# CSR8635-V1_4.net
KiCad netlist of a schematic drawn in EAGLE
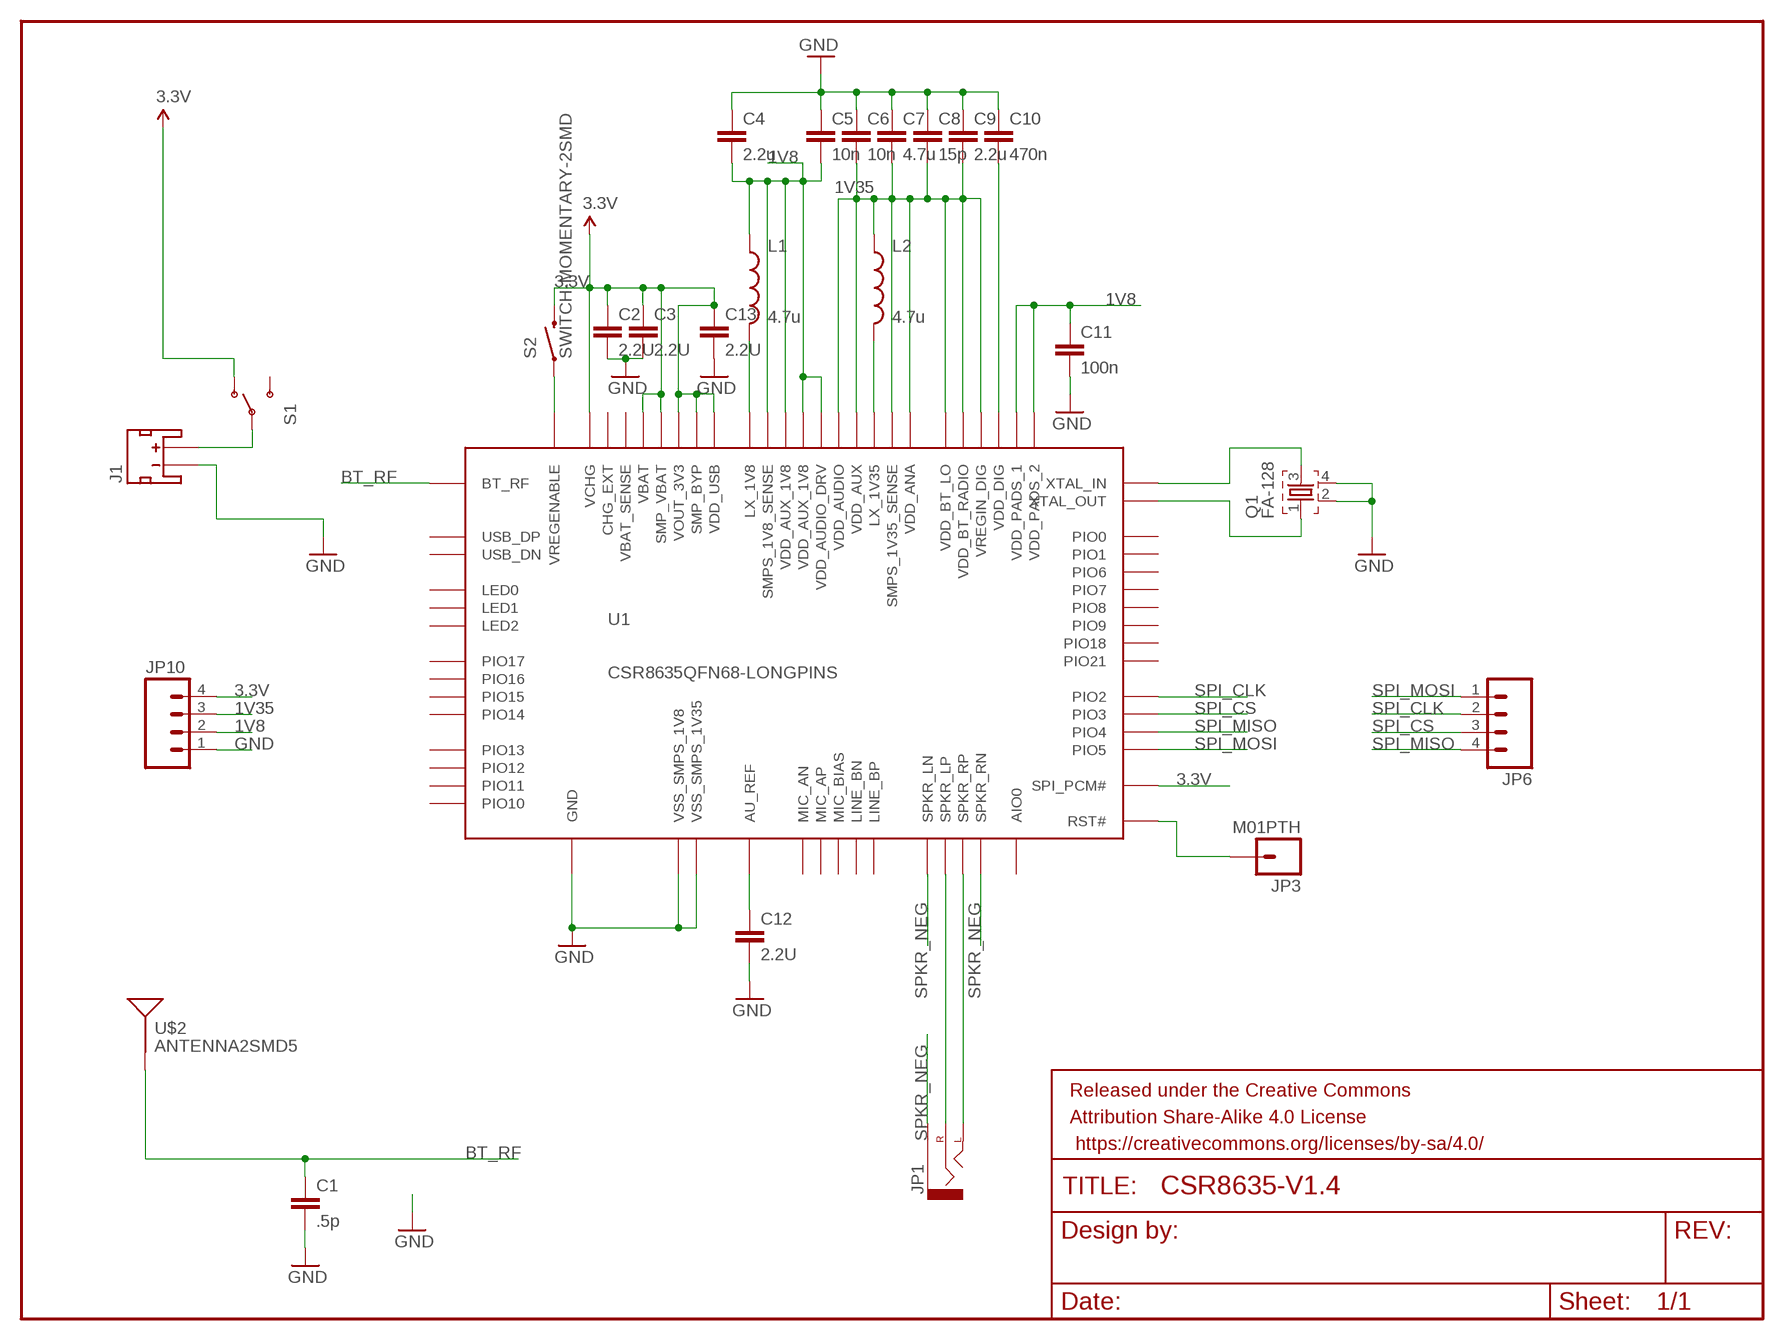
[diagram p0: schematic, sheet 1]

(export (version "E")
  (design (tool "Eeschema 10.0.6"))
  (components
    (comp (ref "C1")
      (value ".5p")
      (footprint "eagle-import:0603-CAP")
      (libsource (lib "eagle-import") (part "CAP0603-CAP"))
    )
    (comp (ref "C2")
      (value "2.2U")
      (footprint "eagle-import:0603-CAP")
      (libsource (lib "eagle-import") (part "CAP0603-CAP"))
    )
    (comp (ref "C3")
      (value "2.2U")
      (footprint "eagle-import:0603-CAP")
      (libsource (lib "eagle-import") (part "CAP0603-CAP"))
    )
    (comp (ref "C4")
      (value "2.2u")
      (footprint "eagle-import:0603-CAP")
      (libsource (lib "eagle-import") (part "CAP0603-CAP"))
    )
    (comp (ref "C5")
      (value "10n")
      (footprint "eagle-import:0603-CAP")
      (libsource (lib "eagle-import") (part "CAP0603-CAP"))
    )
    (comp (ref "C6")
      (value "10n")
      (footprint "eagle-import:0603-CAP")
      (libsource (lib "eagle-import") (part "CAP0603-CAP"))
    )
    (comp (ref "C7")
      (value "4.7u")
      (footprint "eagle-import:0603-CAP")
      (libsource (lib "eagle-import") (part "CAP0603-CAP"))
    )
    (comp (ref "C8")
      (value "15p")
      (footprint "eagle-import:0603-CAP")
      (libsource (lib "eagle-import") (part "CAP0603-CAP"))
    )
    (comp (ref "C9")
      (value "2.2u")
      (footprint "eagle-import:0603-CAP")
      (libsource (lib "eagle-import") (part "CAP0603-CAP"))
    )
    (comp (ref "C10")
      (value "470n")
      (footprint "eagle-import:0603-CAP")
      (libsource (lib "eagle-import") (part "CAP0603-CAP"))
    )
    (comp (ref "C11")
      (value "100n")
      (footprint "eagle-import:0603-CAP")
      (libsource (lib "eagle-import") (part "CAP0603-CAP"))
    )
    (comp (ref "C12")
      (value "2.2U")
      (footprint "eagle-import:0603-CAP")
      (libsource (lib "eagle-import") (part "CAP0603-CAP"))
    )
    (comp (ref "C13")
      (value "2.2U")
      (footprint "eagle-import:0603-CAP")
      (libsource (lib "eagle-import") (part "CAP0603-CAP"))
    )
    (comp (ref "FRAME1")
      (value "FRAME-LETTER")
      (footprint "eagle-import:CREATIVE_COMMONS")
      (libsource (lib "eagle-import") (part "FRAME-LETTER"))
    )
    (comp (ref "J1")
      (value "JST_2MM_MALE")
      (footprint "eagle-import:JST-2-SMD")
      (libsource (lib "eagle-import") (part "JST_2MM_MALE"))
    )
    (comp (ref "JP1")
      (value "AUDIO-JACKSMD2")
      (footprint "eagle-import:AUDIO-JACK-3.5MM-SMD")
      (libsource (lib "eagle-import") (part "AUDIO-JACKSMD2"))
    )
    (comp (ref "JP3")
      (value "M01PTH")
      (footprint "eagle-import:1X01")
      (libsource (lib "eagle-import") (part "M01PTH"))
    )
    (comp (ref "JP6")
      (value "M04PTH")
      (footprint "eagle-import:1X04")
      (libsource (lib "eagle-import") (part "M04PTH"))
    )
    (comp (ref "JP10")
      (value "M04PTH")
      (footprint "eagle-import:1X04")
      (libsource (lib "eagle-import") (part "M04PTH"))
    )
    (comp (ref "L1")
      (value "4.7u")
      (footprint "eagle-import:0805")
      (libsource (lib "eagle-import") (part "INDUCTOR0805"))
    )
    (comp (ref "L2")
      (value "4.7u")
      (footprint "eagle-import:0805")
      (libsource (lib "eagle-import") (part "INDUCTOR0805"))
    )
    (comp (ref "Q1")
      (value "FA-128")
      (footprint "eagle-import:FA-128")
      (libsource (lib "eagle-import") (part "FA-128"))
    )
    (comp (ref "S1")
      (value "SWITCH-SPDTPTH")
      (footprint "eagle-import:SWITCH-SPDT")
      (libsource (lib "eagle-import") (part "SWITCH-SPDTPTH"))
    )
    (comp (ref "S2")
      (value "SWITCH-MOMENTARY-2SMD")
      (footprint "eagle-import:TACTILE-SWITCH-SMD")
      (libsource (lib "eagle-import") (part "SWITCH-MOMENTARY-2SMD"))
    )
    (comp (ref "U$2")
      (value "ANTENNA2SMD5")
      (footprint "eagle-import:ANTENNA-CHIP5")
      (libsource (lib "eagle-import") (part "ANTENNA2SMD5"))
    )
    (comp (ref "U1")
      (value "CSR8635QFN68-LONGPINS")
      (footprint "eagle-import:QFN68")
      (libsource (lib "eagle-import") (part "CSR8635QFN68-LONGPINS"))
    )
  )
  (nets
    (net (code "1") (name "/1V8") (class "Default")
      (node (ref "C11") (pin "1") (pinfunction "1_1") (pintype "passive"))
      (node (ref "C4") (pin "2") (pinfunction "2_2") (pintype "passive"))
      (node (ref "C5") (pin "2") (pinfunction "2_2") (pintype "passive"))
      (node (ref "JP10") (pin "2") (pinfunction "2_2") (pintype "passive"))
      (node (ref "L1") (pin "1") (pinfunction "1_1") (pintype "passive"))
      (node (ref "U1") (pin "15") (pinfunction "VDD_AUX_1V8_15") (pintype "power_in"))
      (node (ref "U1") (pin "16") (pinfunction "VDD_AUX_1V8_16") (pintype "power_in"))
      (node (ref "U1") (pin "33") (pinfunction "VDD_PADS_1_33") (pintype "bidirectional"))
      (node (ref "U1") (pin "53") (pinfunction "SMPS_1V8_SENSE_53") (pintype "bidirectional"))
      (node (ref "U1") (pin "63") (pinfunction "VDD_PADS_2_63") (pintype "power_in"))
      (node (ref "U1") (pin "8") (pinfunction "VDD_AUDIO_DRV_8") (pintype "power_in"))
    )
    (net (code "2") (name "/1V35") (class "Default")
      (node (ref "C6") (pin "2") (pinfunction "2_2") (pintype "passive"))
      (node (ref "C7") (pin "2") (pinfunction "2_2") (pintype "passive"))
      (node (ref "C8") (pin "2") (pinfunction "2_2") (pintype "passive"))
      (node (ref "C9") (pin "2") (pinfunction "2_2") (pintype "passive"))
      (node (ref "JP10") (pin "3") (pinfunction "3_3") (pintype "passive"))
      (node (ref "L2") (pin "1") (pinfunction "1_1") (pintype "passive"))
      (node (ref "U1") (pin "11") (pinfunction "VDD_BT_RADIO_11") (pintype "power_in"))
      (node (ref "U1") (pin "13") (pinfunction "VDD_BT_LO_13") (pintype "power_in"))
      (node (ref "U1") (pin "14") (pinfunction "VDD_AUX_14") (pintype "power_in"))
      (node (ref "U1") (pin "17") (pinfunction "VDD_ANA_17") (pintype "power_in"))
      (node (ref "U1") (pin "3") (pinfunction "VDD_AUDIO_3") (pintype "power_in"))
      (node (ref "U1") (pin "39") (pinfunction "VREGIN_DIG_39") (pintype "bidirectional"))
      (node (ref "U1") (pin "52") (pinfunction "SMPS_1V35_SENSE_52") (pintype "bidirectional"))
    )
    (net (code "3") (name "/BT_RF") (class "Default")
      (node (ref "C1") (pin "1") (pinfunction "1_1") (pintype "passive"))
      (node (ref "U$2") (pin "FEED") (pinfunction "SIGNAL_FEED") (pintype "bidirectional"))
      (node (ref "U1") (pin "12") (pinfunction "BT_RF_12") (pintype "bidirectional"))
    )
    (net (code "4") (name "/SPI_CLK") (class "Default")
      (node (ref "JP6") (pin "2") (pinfunction "2_2") (pintype "passive"))
      (node (ref "U1") (pin "30") (pinfunction "PIO2_30") (pintype "bidirectional"))
    )
    (net (code "5") (name "/SPI_CS") (class "Default")
      (node (ref "JP6") (pin "3") (pinfunction "3_3") (pintype "passive"))
      (node (ref "U1") (pin "28") (pinfunction "PIO3_28") (pintype "bidirectional"))
    )
    (net (code "6") (name "/SPI_MISO") (class "Default")
      (node (ref "JP6") (pin "4") (pinfunction "4_4") (pintype "passive"))
      (node (ref "U1") (pin "24") (pinfunction "PIO4_24") (pintype "bidirectional"))
    )
    (net (code "7") (name "/SPI_MOSI") (class "Default")
      (node (ref "JP6") (pin "1") (pinfunction "1_1") (pintype "passive"))
      (node (ref "U1") (pin "34") (pinfunction "PIO5_34") (pintype "bidirectional"))
    )
    (net (code "8") (name "/SPKR_NEG") (class "Default")
      (node (ref "JP1") (pin "SLEEVE") (pinfunction "SLEEVE_SLEEVE") (pintype "bidirectional"))
      (node (ref "U1") (pin "6") (pinfunction "SPKR_RN_6") (pintype "bidirectional"))
      (node (ref "U1") (pin "9") (pinfunction "SPKR_LN_9") (pintype "bidirectional"))
    )
    (net (code "9") (name "3.3V") (class "Default")
      (node (ref "C13") (pin "1") (pinfunction "1_1") (pintype "passive"))
      (node (ref "C2") (pin "1") (pinfunction "1_1") (pintype "passive"))
      (node (ref "C3") (pin "1") (pinfunction "1_1") (pintype "passive"))
      (node (ref "JP10") (pin "4") (pinfunction "4_4") (pintype "passive"))
      (node (ref "S1") (pin "1") (pinfunction "O_1") (pintype "passive"))
      (node (ref "S2") (pin "3") (pinfunction "2_3") (pintype "passive"))
      (node (ref "U1") (pin "29") (pinfunction "SPI_PCM#_29") (pintype "bidirectional"))
      (node (ref "U1") (pin "41") (pinfunction "VOUT_3V3_41") (pintype "power_in"))
      (node (ref "U1") (pin "42") (pinfunction "VCHG_42") (pintype "bidirectional"))
      (node (ref "U1") (pin "45") (pinfunction "VBAT_45") (pintype "power_in"))
      (node (ref "U1") (pin "48") (pinfunction "SMP_VBAT_48") (pintype "bidirectional"))
      (node (ref "U1") (pin "49") (pinfunction "SMP_BYP_49") (pintype "bidirectional"))
      (node (ref "U1") (pin "54") (pinfunction "VDD_USB_54") (pintype "power_in"))
    )
    (net (code "10") (name "GND") (class "Default")
      (node (ref "C1") (pin "2") (pinfunction "2_2") (pintype "passive"))
      (node (ref "C10") (pin "1") (pinfunction "1_1") (pintype "passive"))
      (node (ref "C11") (pin "2") (pinfunction "2_2") (pintype "passive"))
      (node (ref "C12") (pin "2") (pinfunction "2_2") (pintype "passive"))
      (node (ref "C13") (pin "2") (pinfunction "2_2") (pintype "passive"))
      (node (ref "C2") (pin "2") (pinfunction "2_2") (pintype "passive"))
      (node (ref "C3") (pin "2") (pinfunction "2_2") (pintype "passive"))
      (node (ref "C4") (pin "1") (pinfunction "1_1") (pintype "passive"))
      (node (ref "C5") (pin "1") (pinfunction "1_1") (pintype "passive"))
      (node (ref "C6") (pin "1") (pinfunction "1_1") (pintype "passive"))
      (node (ref "C7") (pin "1") (pinfunction "1_1") (pintype "passive"))
      (node (ref "C8") (pin "1") (pinfunction "1_1") (pintype "passive"))
      (node (ref "C9") (pin "1") (pinfunction "1_1") (pintype "passive"))
      (node (ref "J1") (pin "1") (pinfunction "-_1") (pintype "bidirectional"))
      (node (ref "JP10") (pin "1") (pinfunction "1_1") (pintype "passive"))
      (node (ref "Q1") (pin "2") (pinfunction "2_2") (pintype "passive"))
      (node (ref "Q1") (pin "4") (pinfunction "4_4") (pintype "passive"))
      (node (ref "U1") (pin "46") (pinfunction "VSS_SMPS_1V8_46") (pintype "bidirectional"))
      (node (ref "U1") (pin "51") (pinfunction "VSS_SMPS_1V35_51") (pintype "bidirectional"))
      (node (ref "U1") (pin "CNTR") (pinfunction "GND_CNTR") (pintype "bidirectional"))
      (node (ref "U1") (pin "CNTR1") (pinfunction "GND_CNTR1") (pintype "bidirectional"))
      (node (ref "U1") (pin "CNTR2") (pinfunction "GND_CNTR2") (pintype "bidirectional"))
      (node (ref "U1") (pin "CNTR3") (pinfunction "GND_CNTR3") (pintype "bidirectional"))
    )
    (net (code "11") (name "Net-(J1-+)") (class "Default")
      (node (ref "J1") (pin "2") (pinfunction "+_2") (pintype "bidirectional"))
      (node (ref "S1") (pin "2") (pinfunction "P_2") (pintype "passive"))
    )
    (net (code "12") (name "Net-(JP1-LEFT)") (class "Default")
      (node (ref "JP1") (pin "TIP") (pinfunction "LEFT_TIP") (pintype "bidirectional"))
      (node (ref "U1") (pin "7") (pinfunction "SPKR_RP_7") (pintype "bidirectional"))
    )
    (net (code "13") (name "Net-(JP1-RIGHT)") (class "Default")
      (node (ref "JP1") (pin "RING") (pinfunction "RIGHT_RING") (pintype "bidirectional"))
      (node (ref "U1") (pin "10") (pinfunction "SPKR_LP_10") (pintype "bidirectional"))
    )
    (net (code "14") (name "Net-(U1-AU_REF)") (class "Default")
      (node (ref "C12") (pin "1") (pinfunction "1_1") (pintype "passive"))
      (node (ref "U1") (pin "1") (pinfunction "AU_REF_1") (pintype "bidirectional"))
    )
    (net (code "15") (name "Net-(U1-LX_1V8)") (class "Default")
      (node (ref "L1") (pin "2") (pinfunction "2_2") (pintype "passive"))
      (node (ref "U1") (pin "47") (pinfunction "LX_1V8_47") (pintype "bidirectional"))
    )
    (net (code "16") (name "Net-(U1-LX_1V35)") (class "Default")
      (node (ref "L2") (pin "2") (pinfunction "2_2") (pintype "passive"))
      (node (ref "U1") (pin "50") (pinfunction "LX_1V35_50") (pintype "bidirectional"))
    )
    (net (code "17") (name "Net-(U1-RST#)") (class "Default")
      (node (ref "JP3") (pin "1") (pinfunction "1_1") (pintype "passive"))
      (node (ref "U1") (pin "35") (pinfunction "RST#_35") (pintype "bidirectional"))
    )
    (net (code "18") (name "Net-(U1-VDD_DIG)") (class "Default")
      (node (ref "C10") (pin "2") (pinfunction "2_2") (pintype "passive"))
      (node (ref "U1") (pin "38") (pinfunction "VDD_DIG_38") (pintype "power_in"))
    )
    (net (code "19") (name "Net-(U1-VREGENABLE)") (class "Default")
      (node (ref "S2") (pin "1") (pinfunction "1_1") (pintype "passive"))
      (node (ref "U1") (pin "40") (pinfunction "VREGENABLE_40") (pintype "bidirectional"))
    )
    (net (code "20") (name "Net-(U1-XTAL_IN)") (class "Default")
      (node (ref "Q1") (pin "3") (pinfunction "3_3") (pintype "passive"))
      (node (ref "U1") (pin "19") (pinfunction "XTAL_IN_19") (pintype "bidirectional"))
    )
    (net (code "21") (name "Net-(U1-XTAL_OUT)") (class "Default")
      (node (ref "Q1") (pin "1") (pinfunction "1_1") (pintype "passive"))
      (node (ref "U1") (pin "18") (pinfunction "XTAL_OUT_18") (pintype "bidirectional"))
    )
    (net (code "22") (name "unconnected-(J1-PAD1-PadNC1)") (class "Default")
      (node (ref "J1") (pin "NC1") (pinfunction "PAD1_NC1") (pintype "bidirectional"))
    )
    (net (code "23") (name "unconnected-(J1-PAD2-PadNC2)") (class "Default")
      (node (ref "J1") (pin "NC2") (pinfunction "PAD2_NC2") (pintype "bidirectional"))
    )
    (net (code "24") (name "unconnected-(S1-S-Pad3)") (class "Default")
      (node (ref "S1") (pin "3") (pinfunction "S_3") (pintype "passive"))
    )
    (net (code "25") (name "unconnected-(U1-AIO0-Pad20)") (class "Default")
      (node (ref "U1") (pin "20") (pinfunction "AIO0_20") (pintype "bidirectional"))
    )
    (net (code "26") (name "unconnected-(U1-CHG_EXT-Pad43)") (class "Default")
      (node (ref "U1") (pin "43") (pinfunction "CHG_EXT_43") (pintype "bidirectional"))
    )
    (net (code "27") (name "unconnected-(U1-LED0-Pad37)") (class "Default")
      (node (ref "U1") (pin "37") (pinfunction "LED0_37") (pintype "bidirectional"))
    )
    (net (code "28") (name "unconnected-(U1-LED1-Pad36)") (class "Default")
      (node (ref "U1") (pin "36") (pinfunction "LED1_36") (pintype "bidirectional"))
    )
    (net (code "29") (name "unconnected-(U1-LED2-Pad66)") (class "Default")
      (node (ref "U1") (pin "66") (pinfunction "LED2_66") (pintype "bidirectional"))
    )
    (net (code "30") (name "unconnected-(U1-LINE_BN-Pad4)") (class "Default")
      (node (ref "U1") (pin "4") (pinfunction "LINE_BN_4") (pintype "bidirectional"))
    )
    (net (code "31") (name "unconnected-(U1-LINE_BP-Pad5)") (class "Default")
      (node (ref "U1") (pin "5") (pinfunction "LINE_BP_5") (pintype "bidirectional"))
    )
    (net (code "32") (name "unconnected-(U1-MIC_AN-Pad67)") (class "Default")
      (node (ref "U1") (pin "67") (pinfunction "MIC_AN_67") (pintype "bidirectional"))
    )
    (net (code "33") (name "unconnected-(U1-MIC_AP-Pad68)") (class "Default")
      (node (ref "U1") (pin "68") (pinfunction "MIC_AP_68") (pintype "bidirectional"))
    )
    (net (code "34") (name "unconnected-(U1-MIC_BIAS-Pad2)") (class "Default")
      (node (ref "U1") (pin "2") (pinfunction "MIC_BIAS_2") (pintype "bidirectional"))
    )
    (net (code "35") (name "unconnected-(U1-PIO0-Pad59)") (class "Default")
      (node (ref "U1") (pin "59") (pinfunction "PIO0_59") (pintype "bidirectional"))
    )
    (net (code "36") (name "unconnected-(U1-PIO1-Pad60)") (class "Default")
      (node (ref "U1") (pin "60") (pinfunction "PIO1_60") (pintype "bidirectional"))
    )
    (net (code "37") (name "unconnected-(U1-PIO6-Pad62)") (class "Default")
      (node (ref "U1") (pin "62") (pinfunction "PIO6_62") (pintype "bidirectional"))
    )
    (net (code "38") (name "unconnected-(U1-PIO7-Pad57)") (class "Default")
      (node (ref "U1") (pin "57") (pinfunction "PIO7_57") (pintype "bidirectional"))
    )
    (net (code "39") (name "unconnected-(U1-PIO8-Pad61)") (class "Default")
      (node (ref "U1") (pin "61") (pinfunction "PIO8_61") (pintype "bidirectional"))
    )
    (net (code "40") (name "unconnected-(U1-PIO9-Pad58)") (class "Default")
      (node (ref "U1") (pin "58") (pinfunction "PIO9_58") (pintype "bidirectional"))
    )
    (net (code "41") (name "unconnected-(U1-PIO10-Pad25)") (class "Default")
      (node (ref "U1") (pin "25") (pinfunction "PIO10_25") (pintype "bidirectional"))
    )
    (net (code "42") (name "unconnected-(U1-PIO11-Pad26)") (class "Default")
      (node (ref "U1") (pin "26") (pinfunction "PIO11_26") (pintype "bidirectional"))
    )
    (net (code "43") (name "unconnected-(U1-PIO12-Pad22)") (class "Default")
      (node (ref "U1") (pin "22") (pinfunction "PIO12_22") (pintype "bidirectional"))
    )
    (net (code "44") (name "unconnected-(U1-PIO13-Pad31)") (class "Default")
      (node (ref "U1") (pin "31") (pinfunction "PIO13_31") (pintype "bidirectional"))
    )
    (net (code "45") (name "unconnected-(U1-PIO14-Pad23)") (class "Default")
      (node (ref "U1") (pin "23") (pinfunction "PIO14_23") (pintype "bidirectional"))
    )
    (net (code "46") (name "unconnected-(U1-PIO15-Pad21)") (class "Default")
      (node (ref "U1") (pin "21") (pinfunction "PIO15_21") (pintype "bidirectional"))
    )
    (net (code "47") (name "unconnected-(U1-PIO16-Pad27)") (class "Default")
      (node (ref "U1") (pin "27") (pinfunction "PIO16_27") (pintype "bidirectional"))
    )
    (net (code "48") (name "unconnected-(U1-PIO17-Pad32)") (class "Default")
      (node (ref "U1") (pin "32") (pinfunction "PIO17_32") (pintype "bidirectional"))
    )
    (net (code "49") (name "unconnected-(U1-PIO18-Pad65)") (class "Default")
      (node (ref "U1") (pin "65") (pinfunction "PIO18_65") (pintype "bidirectional"))
    )
    (net (code "50") (name "unconnected-(U1-PIO21-Pad64)") (class "Default")
      (node (ref "U1") (pin "64") (pinfunction "PIO21_64") (pintype "bidirectional"))
    )
    (net (code "51") (name "unconnected-(U1-USB_DN-Pad55)") (class "Default")
      (node (ref "U1") (pin "55") (pinfunction "USB_DN_55") (pintype "bidirectional"))
    )
    (net (code "52") (name "unconnected-(U1-USB_DP-Pad56)") (class "Default")
      (node (ref "U1") (pin "56") (pinfunction "USB_DP_56") (pintype "bidirectional"))
    )
    (net (code "53") (name "unconnected-(U1-VBAT_SENSE-Pad44)") (class "Default")
      (node (ref "U1") (pin "44") (pinfunction "VBAT_SENSE_44") (pintype "bidirectional"))
    )
  )
)
